# PlanktoscopeHat-v0_1-fab.net
KiCad netlist of a schematic drawn in EAGLE
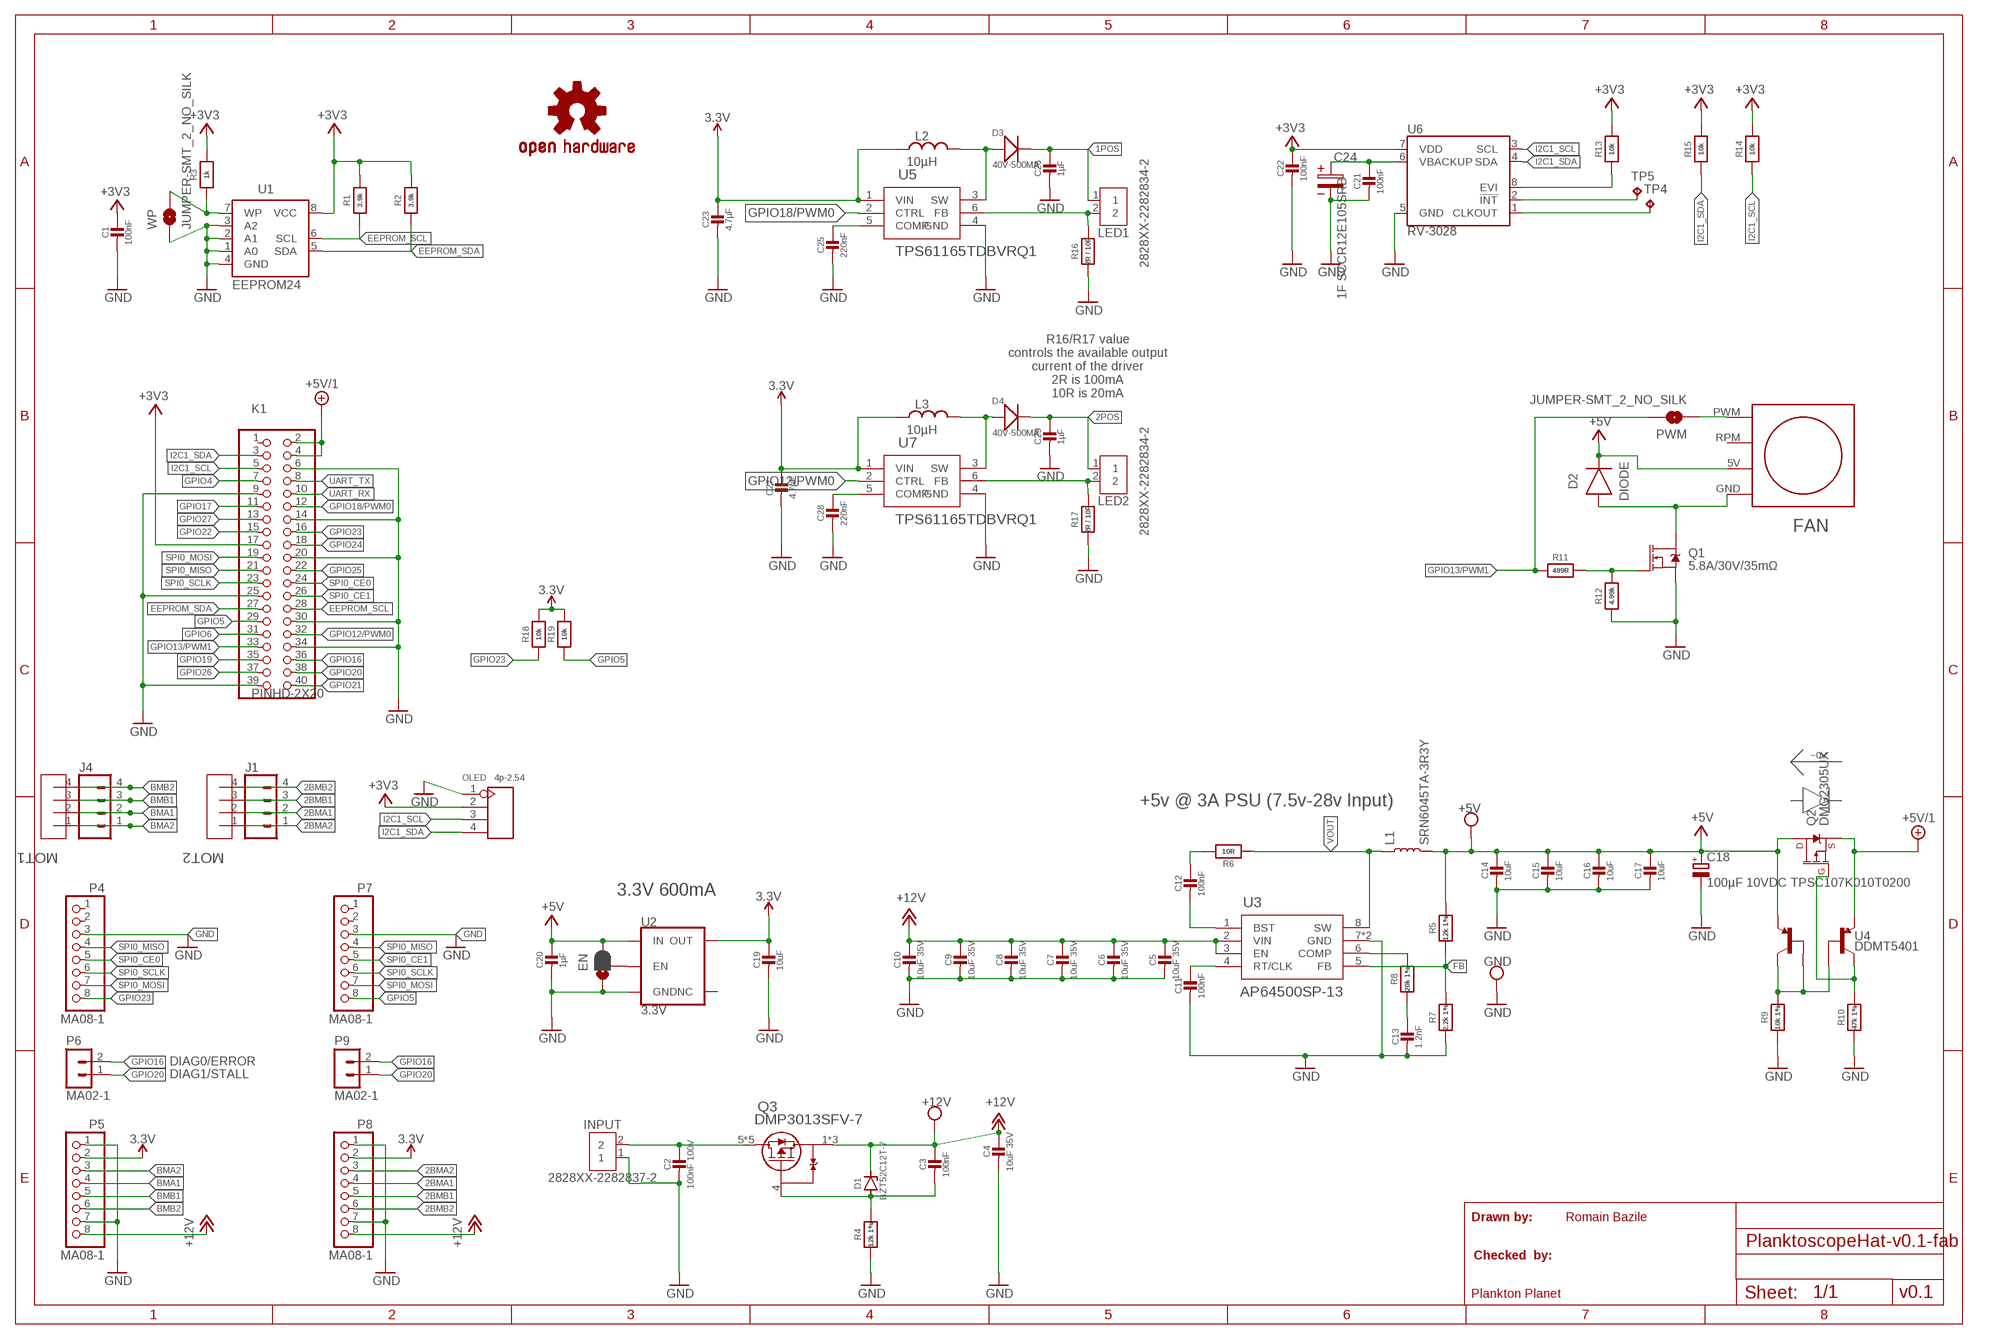
[diagram p0: schematic, sheet 1]

(export (version "E")
  (design (tool "Eeschema 10.0.6"))
  (components
    (comp (ref "+5V")
      (value "TESTPOINTPAD2MM")
      (footprint "eagle-import:TESTPOINT_PAD_2MM")
      (libsource (lib "eagle-import") (part "TESTPOINTPAD2MM"))
    )
    (comp (ref "+12V")
      (value "TESTPOINTPAD2MM")
      (footprint "eagle-import:TESTPOINT_PAD_2MM")
      (libsource (lib "eagle-import") (part "TESTPOINTPAD2MM"))
    )
    (comp (ref "C1")
      (value "100nF")
      (footprint "eagle-import:_0805MP")
      (libsource (lib "eagle-import") (part "CAP_CERAMIC_0805MP"))
    )
    (comp (ref "C2")
      (value "100nF 100V")
      (footprint "eagle-import:_0805MP")
      (libsource (lib "eagle-import") (part "CAP_CERAMIC_0805MP"))
    )
    (comp (ref "C3")
      (value "100nF")
      (footprint "eagle-import:_0805MP")
      (libsource (lib "eagle-import") (part "CAP_CERAMIC_0805MP"))
    )
    (comp (ref "C4")
      (value "10uF 35V")
      (footprint "eagle-import:_0805MP")
      (libsource (lib "eagle-import") (part "CAP_CERAMIC_0805MP"))
    )
    (comp (ref "C5")
      (value "10uF 35V")
      (footprint "eagle-import:_0805MP")
      (libsource (lib "eagle-import") (part "CAP_CERAMIC_0805MP"))
    )
    (comp (ref "C6")
      (value "10uF 35V")
      (footprint "eagle-import:_0805MP")
      (libsource (lib "eagle-import") (part "CAP_CERAMIC_0805MP"))
    )
    (comp (ref "C7")
      (value "10uF 35V")
      (footprint "eagle-import:_0805MP")
      (libsource (lib "eagle-import") (part "CAP_CERAMIC_0805MP"))
    )
    (comp (ref "C8")
      (value "10uF 35V")
      (footprint "eagle-import:_0805MP")
      (libsource (lib "eagle-import") (part "CAP_CERAMIC_0805MP"))
    )
    (comp (ref "C9")
      (value "10uF 35V")
      (footprint "eagle-import:_0805MP")
      (libsource (lib "eagle-import") (part "CAP_CERAMIC_0805MP"))
    )
    (comp (ref "C10")
      (value "10uF 35V")
      (footprint "eagle-import:_0805MP")
      (libsource (lib "eagle-import") (part "CAP_CERAMIC_0805MP"))
    )
    (comp (ref "C11")
      (value "100nF")
      (footprint "eagle-import:_0805MP")
      (libsource (lib "eagle-import") (part "CAP_CERAMIC_0805MP"))
    )
    (comp (ref "C12")
      (value "100nF")
      (footprint "eagle-import:_0805MP")
      (libsource (lib "eagle-import") (part "CAP_CERAMIC_0805MP"))
    )
    (comp (ref "C13")
      (value "1.2nF")
      (footprint "eagle-import:_0805MP")
      (libsource (lib "eagle-import") (part "CAP_CERAMIC_0805MP"))
    )
    (comp (ref "C14")
      (value "10uF")
      (footprint "eagle-import:_0805MP")
      (libsource (lib "eagle-import") (part "CAP_CERAMIC_0805MP"))
    )
    (comp (ref "C15")
      (value "10uF")
      (footprint "eagle-import:_0805MP")
      (libsource (lib "eagle-import") (part "CAP_CERAMIC_0805MP"))
    )
    (comp (ref "C16")
      (value "10uF")
      (footprint "eagle-import:_0805MP")
      (libsource (lib "eagle-import") (part "CAP_CERAMIC_0805MP"))
    )
    (comp (ref "C17")
      (value "10uF")
      (footprint "eagle-import:_0805MP")
      (libsource (lib "eagle-import") (part "CAP_CERAMIC_0805MP"))
    )
    (comp (ref "C18")
      (value "100µF 10VDC TPSC107K010T0200")
      (footprint "eagle-import:CAPMP6032X280N")
      (libsource (lib "eagle-import") (part "C-POLTANTALUM-2412(6032-METRIC)_"))
    )
    (comp (ref "C19")
      (value "10uF")
      (footprint "eagle-import:_0805MP")
      (libsource (lib "eagle-import") (part "CAP_CERAMIC_0805MP"))
    )
    (comp (ref "C20")
      (value "1µF")
      (footprint "eagle-import:_0805MP")
      (libsource (lib "eagle-import") (part "CAP_CERAMIC_0805MP"))
    )
    (comp (ref "C21")
      (value "100nF")
      (footprint "eagle-import:_0805MP")
      (libsource (lib "eagle-import") (part "CAP_CERAMIC_0805MP"))
    )
    (comp (ref "C22")
      (value "100nF")
      (footprint "eagle-import:_0805MP")
      (libsource (lib "eagle-import") (part "CAP_CERAMIC_0805MP"))
    )
    (comp (ref "C23")
      (value "4.7µF")
      (footprint "eagle-import:_0805MP")
      (libsource (lib "eagle-import") (part "CAP_CERAMIC_0805MP"))
    )
    (comp (ref "C24")
      (value "1F SCCR12E105SRB")
      (footprint "eagle-import:8X3.5X0.9(DXAXB)")
      (libsource (lib "eagle-import") (part "WCAP-PTHT_870135174001_8X8"))
    )
    (comp (ref "C25")
      (value "220nF")
      (footprint "eagle-import:_0805MP")
      (libsource (lib "eagle-import") (part "CAP_CERAMIC_0805MP"))
    )
    (comp (ref "C26")
      (value "1µF")
      (footprint "eagle-import:_0805MP")
      (libsource (lib "eagle-import") (part "CAP_CERAMIC_0805MP"))
    )
    (comp (ref "C27")
      (value "4.7µF")
      (footprint "eagle-import:_0805MP")
      (libsource (lib "eagle-import") (part "CAP_CERAMIC_0805MP"))
    )
    (comp (ref "C28")
      (value "220nF")
      (footprint "eagle-import:_0805MP")
      (libsource (lib "eagle-import") (part "CAP_CERAMIC_0805MP"))
    )
    (comp (ref "C29")
      (value "1µF")
      (footprint "eagle-import:_0805MP")
      (libsource (lib "eagle-import") (part "CAP_CERAMIC_0805MP"))
    )
    (comp (ref "D1")
      (value "BZT52C12T-7")
      (footprint "eagle-import:SODFL1608X70")
      (libsource (lib "eagle-import") (part "ZENERSODFL(1608-METRIC)_"))
    )
    (comp (ref "D2")
      (value "DIODE")
      (footprint "eagle-import:DIOM5226X290N")
      (libsource (lib "eagle-import") (part "DIODEDO-214AC(SMA)"))
    )
    (comp (ref "D3")
      (value "40V-500MA")
      (footprint "eagle-import:SOD-123")
      (fields (field (name "MPN") "B0540W"))
      (libsource (lib "eagle-import") (part "SMD-DIODE-SCHOTTKY-40V-500MA(SOD-123)"))
    )
    (comp (ref "D4")
      (value "40V-500MA")
      (footprint "eagle-import:SOD-123")
      (fields (field (name "MPN") "B0540W"))
      (libsource (lib "eagle-import") (part "SMD-DIODE-SCHOTTKY-40V-500MA(SOD-123)"))
    )
    (comp (ref "EN")
      (value "JUMPER-SMT_3_1-NC_PASTE_SILK")
      (footprint "eagle-import:SMT-JUMPER_3_1-NC_PASTE_SILK")
      (libsource (lib "eagle-import") (part "JUMPER-SMT_3_1-NC_PASTE_SILK"))
    )
    (comp (ref "FAN")
      (value "40MM_FAN")
      (footprint "eagle-import:40MM_FAN")
      (libsource (lib "eagle-import") (part "40MM_FAN"))
    )
    (comp (ref "GND")
      (value "TESTPOINTPAD2MM")
      (footprint "eagle-import:TESTPOINT_PAD_2MM")
      (libsource (lib "eagle-import") (part "TESTPOINTPAD2MM"))
    )
    (comp (ref "INPUT")
      (value "2828XX-2282837-2")
      (footprint "eagle-import:TERMBLK_508-2N")
      (fields
        (field (name "MANUFACTURER") "TE Connectivity")
        (field (name "MPN") "282837-2")
        (field (name "MPN_1") "TC0203620000G")
      )
      (libsource (lib "eagle-import") (part "2828XX-2282837-2"))
    )
    (comp (ref "J1")
      (value "CONN_04SCREW")
      (footprint "eagle-import:SCREWTERMINAL-3.5MM-4")
      (libsource (lib "eagle-import") (part "CONN_04SCREW"))
    )
    (comp (ref "J4")
      (value "CONN_04SCREW")
      (footprint "eagle-import:SCREWTERMINAL-3.5MM-4")
      (libsource (lib "eagle-import") (part "CONN_04SCREW"))
    )
    (comp (ref "K1")
      (value "PINHD-2X20")
      (footprint "eagle-import:2X20")
      (libsource (lib "eagle-import") (part "PINHD-2X20"))
    )
    (comp (ref "L1")
      (value "SRN6045TA-3R3Y")
      (footprint "eagle-import:SRN6045")
      (libsource (lib "eagle-import") (part "INDUCTOR-SRN6045-33UH"))
    )
    (comp (ref "L2")
      (value "10µH")
      (footprint "eagle-import:INDM3225X240")
      (fields (field (name "MPN") "CBC3225T100KR"))
      (libsource (lib "eagle-import") (part "LMOLDED-1210(3225-METRIC)_"))
    )
    (comp (ref "L3")
      (value "10µH")
      (footprint "eagle-import:INDM3225X240")
      (fields (field (name "MPN") "CBC3225T100KR"))
      (libsource (lib "eagle-import") (part "LMOLDED-1210(3225-METRIC)_"))
    )
    (comp (ref "LED1")
      (value "2828XX-2282834-2")
      (footprint "eagle-import:TERMBLK_254-2N")
      (libsource (lib "eagle-import") (part "2828XX-2282834-2"))
    )
    (comp (ref "LED2")
      (value "2828XX-2282834-2")
      (footprint "eagle-import:TERMBLK_254-2N")
      (libsource (lib "eagle-import") (part "2828XX-2282834-2"))
    )
    (comp (ref "LOGO1")
      (value "OSHW-LOGOL-COPPER")
      (footprint "eagle-import:OSHW-LOGO-L_COPPER")
      (libsource (lib "eagle-import") (part "OSHW-LOGOL-COPPER"))
    )
    (comp (ref "MOT1")
      (value "S4B-XH-SM4-TB(LF)(SN)")
      (footprint "eagle-import:CONN_S4B-XH-SM4-TB_JST")
      (fields (field (name "COPYRIGHT") "Copyright (C) 2018 Accelerated Designs. All rights reserved"))
      (libsource (lib "eagle-import") (part "S4B-XH-SM4-TB(LF)(SN)"))
    )
    (comp (ref "MOT2")
      (value "S4B-XH-SM4-TB(LF)(SN)")
      (footprint "eagle-import:CONN_S4B-XH-SM4-TB_JST")
      (fields (field (name "COPYRIGHT") "Copyright (C) 2018 Accelerated Designs. All rights reserved"))
      (libsource (lib "eagle-import") (part "S4B-XH-SM4-TB(LF)(SN)"))
    )
    (comp (ref "OLED")
      (value "4p-2.54")
      (footprint "eagle-import:H4-2.54")
      (fields (field (name "MPN") "P125-1104A0BS116A1"))
      (libsource (lib "eagle-import") (part "DIP-BLACK-MALE-HEADER-VERT(4P-2.54)"))
    )
    (comp (ref "P4")
      (value "MA08-1")
      (footprint "eagle-import:1X08-S")
      (libsource (lib "eagle-import") (part "PINHD-1X08_2.54-S"))
    )
    (comp (ref "P5")
      (value "MA08-1")
      (footprint "eagle-import:1X08-S")
      (libsource (lib "eagle-import") (part "PINHD-1X08_2.54-S"))
    )
    (comp (ref "P6")
      (value "MA02-1")
      (footprint "eagle-import:MA02-1")
      (libsource (lib "eagle-import") (part "MA02-1"))
    )
    (comp (ref "P7")
      (value "MA08-1")
      (footprint "eagle-import:1X08-S")
      (libsource (lib "eagle-import") (part "PINHD-1X08_2.54-S"))
    )
    (comp (ref "P8")
      (value "MA08-1")
      (footprint "eagle-import:1X08-S")
      (libsource (lib "eagle-import") (part "PINHD-1X08_2.54-S"))
    )
    (comp (ref "P9")
      (value "MA02-1")
      (footprint "eagle-import:MA02-1")
      (libsource (lib "eagle-import") (part "MA02-1"))
    )
    (comp (ref "PWM")
      (value "JUMPER-SMT_2_NO_SILK")
      (footprint "eagle-import:SMT-JUMPER_2_NO_SILK")
      (libsource (lib "eagle-import") (part "JUMPER-SMT_2_NO_SILK"))
    )
    (comp (ref "Q1")
      (value "5.8A/30V/35mΩ")
      (footprint "eagle-import:SOT23-3")
      (libsource (lib "eagle-import") (part "MOSFET-NCH-AO3404A"))
    )
    (comp (ref "Q2")
      (value "DMG2305UX")
      (footprint "eagle-import:SOT23-3")
      (libsource (lib "eagle-import") (part "MOSFET_PCH-DMG2305UX-7"))
    )
    (comp (ref "Q3")
      (value "DMP3013SFV-7")
      (footprint "eagle-import:POWERDI3333-8_UX_DIO")
      (fields (field (name "COPYRIGHT") "Copyright (C) 2018 Accelerated Designs. All rights reserved"))
      (libsource (lib "eagle-import") (part "DMP3013SFV-7"))
    )
    (comp (ref "R1")
      (value "3.9k")
      (footprint "eagle-import:_0805MP")
      (libsource (lib "eagle-import") (part "RESISTOR_0805MP"))
    )
    (comp (ref "R2")
      (value "3.9k")
      (footprint "eagle-import:_0805MP")
      (libsource (lib "eagle-import") (part "RESISTOR_0805MP"))
    )
    (comp (ref "R3")
      (value "1k")
      (footprint "eagle-import:_0805MP")
      (libsource (lib "eagle-import") (part "RESISTOR_0805MP"))
    )
    (comp (ref "R4")
      (value "12k 1%")
      (footprint "eagle-import:_0805MP")
      (libsource (lib "eagle-import") (part "RESISTOR_0805MP"))
    )
    (comp (ref "R5")
      (value "12k 1%")
      (footprint "eagle-import:_0805MP")
      (libsource (lib "eagle-import") (part "RESISTOR_0805MP"))
    )
    (comp (ref "R6")
      (value "10R")
      (footprint "eagle-import:_0805MP")
      (libsource (lib "eagle-import") (part "RESISTOR_0805MP"))
    )
    (comp (ref "R7")
      (value "2.2k 1%")
      (footprint "eagle-import:_0805MP")
      (libsource (lib "eagle-import") (part "RESISTOR_0805MP"))
    )
    (comp (ref "R8")
      (value "20k 1%")
      (footprint "eagle-import:_0805MP")
      (libsource (lib "eagle-import") (part "RESISTOR_0805MP"))
    )
    (comp (ref "R9")
      (value "10k 1%")
      (footprint "eagle-import:_0805MP")
      (libsource (lib "eagle-import") (part "RESISTOR_0805MP"))
    )
    (comp (ref "R10")
      (value "47k 1%")
      (footprint "eagle-import:_0805MP")
      (libsource (lib "eagle-import") (part "RESISTOR_0805MP"))
    )
    (comp (ref "R11")
      (value "499R")
      (footprint "eagle-import:_0805MP")
      (libsource (lib "eagle-import") (part "RESISTOR_0805MP"))
    )
    (comp (ref "R12")
      (value "4.99k")
      (footprint "eagle-import:_0805MP")
      (libsource (lib "eagle-import") (part "RESISTOR_0805MP"))
    )
    (comp (ref "R13")
      (value "10k")
      (footprint "eagle-import:_0805MP")
      (libsource (lib "eagle-import") (part "RESISTOR_0805MP"))
    )
    (comp (ref "R14")
      (value "10k")
      (footprint "eagle-import:_0805MP")
      (libsource (lib "eagle-import") (part "RESISTOR_0805MP"))
    )
    (comp (ref "R15")
      (value "10k")
      (footprint "eagle-import:_0805MP")
      (libsource (lib "eagle-import") (part "RESISTOR_0805MP"))
    )
    (comp (ref "R16")
      (value "2R / 10R")
      (footprint "eagle-import:_0805MP")
      (libsource (lib "eagle-import") (part "RESISTOR_0805MP"))
    )
    (comp (ref "R17")
      (value "2R / 10R")
      (footprint "eagle-import:_0805MP")
      (libsource (lib "eagle-import") (part "RESISTOR_0805MP"))
    )
    (comp (ref "R18")
      (value "10k")
      (footprint "eagle-import:_0805MP")
      (libsource (lib "eagle-import") (part "RESISTOR_0805MP"))
    )
    (comp (ref "R19")
      (value "10k")
      (footprint "eagle-import:_0805MP")
      (libsource (lib "eagle-import") (part "RESISTOR_0805MP"))
    )
    (comp (ref "TP4")
      (value "TPB1,27")
      (footprint "eagle-import:B1,27")
      (libsource (lib "eagle-import") (part "TPB1,27"))
    )
    (comp (ref "TP5")
      (value "TPB1,27")
      (footprint "eagle-import:B1,27")
      (libsource (lib "eagle-import") (part "TPB1,27"))
    )
    (comp (ref "U1")
      (value "EEPROM24")
      (footprint "eagle-import:SOIC8")
      (libsource (lib "eagle-import") (part "EEPROM24"))
    )
    (comp (ref "U2")
      (value "3.3V")
      (footprint "eagle-import:SOT23-5")
      (libsource (lib "eagle-import") (part "V_REG_AP2112K-3.3V"))
    )
    (comp (ref "U3")
      (value "AP64500SP-13")
      (footprint "eagle-import:SO-8EP_DIO")
      (fields (field (name "COPYRIGHT") "Copyright (C) 2018 Accelerated Designs. All rights reserved"))
      (libsource (lib "eagle-import") (part "AP64500SP-13"))
    )
    (comp (ref "U4")
      (value "DDMT5401")
      (footprint "eagle-import:SOT26")
      (libsource (lib "eagle-import") (part "DDMT5401"))
    )
    (comp (ref "U5")
      (value "TPS61165TDBVRQ1")
      (footprint "eagle-import:DBV6")
      (fields
        (field (name "GENERIC_PART_NUMBER") "TPS61165-Q1")
        (field (name "MANUFACTURER") "Texas Instruments")
      )
      (libsource (lib "eagle-import") (part "TPS61165TDBVRQ1"))
    )
    (comp (ref "U6")
      (value "RV-3028")
      (footprint "eagle-import:RV-3028")
      (libsource (lib "eagle-import") (part "RV-3028"))
    )
    (comp (ref "U7")
      (value "TPS61165TDBVRQ1")
      (footprint "eagle-import:DBV6")
      (fields
        (field (name "GENERIC_PART_NUMBER") "TPS61165-Q1")
        (field (name "MANUFACTURER") "Texas Instruments")
      )
      (libsource (lib "eagle-import") (part "TPS61165TDBVRQ1"))
    )
    (comp (ref "WP")
      (value "JUMPER-SMT_2_NO_SILK")
      (footprint "eagle-import:SMT-JUMPER_2_NO_SILK")
      (libsource (lib "eagle-import") (part "JUMPER-SMT_2_NO_SILK"))
    )
  )
  (nets
    (net (code "1") (name "+3V3") (class "Default")
      (node (ref "C1") (pin "1") (pinfunction "1_1") (pintype "passive"))
      (node (ref "C22") (pin "1") (pinfunction "1_1") (pintype "passive"))
      (node (ref "K1") (pin "17") (pinfunction "17_17") (pintype "passive"))
      (node (ref "OLED") (pin "2") (pinfunction "P$2_2") (pintype "bidirectional"))
      (node (ref "R1") (pin "2") (pinfunction "2_2") (pintype "passive"))
      (node (ref "R13") (pin "2") (pinfunction "2_2") (pintype "passive"))
      (node (ref "R14") (pin "2") (pinfunction "2_2") (pintype "passive"))
      (node (ref "R15") (pin "2") (pinfunction "2_2") (pintype "passive"))
      (node (ref "R2") (pin "2") (pinfunction "2_2") (pintype "passive"))
      (node (ref "R3") (pin "2") (pinfunction "2_2") (pintype "passive"))
      (node (ref "U1") (pin "8") (pinfunction "VCC_8") (pintype "power_in"))
      (node (ref "U6") (pin "7") (pinfunction "VDD_7") (pintype "bidirectional"))
    )
    (net (code "2") (name "+5V") (class "Default")
      (node (ref "+5V") (pin "P$1") (pinfunction "P$1_P$1") (pintype "bidirectional"))
      (node (ref "C14") (pin "1") (pinfunction "1_1") (pintype "passive"))
      (node (ref "C15") (pin "1") (pinfunction "1_1") (pintype "passive"))
      (node (ref "C16") (pin "1") (pinfunction "1_1") (pintype "passive"))
      (node (ref "C17") (pin "1") (pinfunction "1_1") (pintype "passive"))
      (node (ref "C18") (pin "1") (pinfunction "+_1") (pintype "passive"))
      (node (ref "C20") (pin "1") (pinfunction "1_1") (pintype "passive"))
      (node (ref "D2") (pin "1") (pinfunction "C_1") (pintype "passive"))
      (node (ref "EN") (pin "3") (pinfunction "3_3") (pintype "passive"))
      (node (ref "FAN") (pin "5V") (pinfunction "+5V_5V") (pintype "passive"))
      (node (ref "L1") (pin "2") (pinfunction "2_2") (pintype "passive"))
      (node (ref "Q2") (pin "3") (pinfunction "D_3") (pintype "bidirectional"))
      (node (ref "R5") (pin "2") (pinfunction "2_2") (pintype "passive"))
      (node (ref "U2") (pin "1") (pinfunction "IN_1") (pintype "input"))
      (node (ref "U4") (pin "D1") (pinfunction "6_D1") (pintype "passive"))
    )
    (net (code "3") (name "+5V{slash}1") (class "Default")
      (node (ref "K1") (pin "2") (pinfunction "2_2") (pintype "passive"))
      (node (ref "K1") (pin "4") (pinfunction "4_4") (pintype "passive"))
      (node (ref "Q2") (pin "2") (pinfunction "S_2") (pintype "bidirectional"))
      (node (ref "U4") (pin "S1") (pinfunction "5_S1") (pintype "passive"))
    )
    (net (code "4") (name "+12V") (class "Default")
      (node (ref "+12V") (pin "P$1") (pinfunction "P$1_P$1") (pintype "bidirectional"))
      (node (ref "C10") (pin "1") (pinfunction "1_1") (pintype "passive"))
      (node (ref "C3") (pin "1") (pinfunction "1_1") (pintype "passive"))
      (node (ref "C4") (pin "1") (pinfunction "1_1") (pintype "passive"))
      (node (ref "C5") (pin "1") (pinfunction "1_1") (pintype "passive"))
      (node (ref "C6") (pin "1") (pinfunction "1_1") (pintype "passive"))
      (node (ref "C7") (pin "1") (pinfunction "1_1") (pintype "passive"))
      (node (ref "C8") (pin "1") (pinfunction "1_1") (pintype "passive"))
      (node (ref "C9") (pin "1") (pinfunction "1_1") (pintype "passive"))
      (node (ref "D1") (pin "1") (pinfunction "C_1") (pintype "passive"))
      (node (ref "P5") (pin "8") (pinfunction "8_8") (pintype "passive"))
      (node (ref "P8") (pin "8") (pinfunction "8_8") (pintype "passive"))
      (node (ref "Q3") (pin "1") (pinfunction "S_1") (pintype "passive"))
      (node (ref "Q3") (pin "2") (pinfunction "S_2") (pintype "passive"))
      (node (ref "Q3") (pin "3") (pinfunction "S_3") (pintype "passive"))
      (node (ref "U3") (pin "2") (pinfunction "VIN_2") (pintype "power_in"))
      (node (ref "U3") (pin "3") (pinfunction "EN_3") (pintype "input"))
    )
    (net (code "5") (name "1POS") (class "Default")
      (node (ref "C26") (pin "1") (pinfunction "1_1") (pintype "passive"))
      (node (ref "D3") (pin "-") (pinfunction "-_-") (pintype "passive"))
      (node (ref "LED1") (pin "1") (pinfunction "1_1") (pintype "bidirectional"))
    )
    (net (code "6") (name "2BMA1") (class "Default")
      (node (ref "J1") (pin "2") (pinfunction "2_2") (pintype "passive"))
      (node (ref "MOT2") (pin "2") (pinfunction "2_2") (pintype "passive"))
      (node (ref "P8") (pin "4") (pinfunction "4_4") (pintype "passive"))
    )
    (net (code "7") (name "2BMA2") (class "Default")
      (node (ref "J1") (pin "1") (pinfunction "1_1") (pintype "passive"))
      (node (ref "MOT2") (pin "1") (pinfunction "1_1") (pintype "passive"))
      (node (ref "P8") (pin "3") (pinfunction "3_3") (pintype "passive"))
    )
    (net (code "8") (name "2BMB1") (class "Default")
      (node (ref "J1") (pin "3") (pinfunction "3_3") (pintype "passive"))
      (node (ref "MOT2") (pin "3") (pinfunction "3_3") (pintype "passive"))
      (node (ref "P8") (pin "5") (pinfunction "5_5") (pintype "passive"))
    )
    (net (code "9") (name "2BMB2") (class "Default")
      (node (ref "J1") (pin "4") (pinfunction "4_4") (pintype "passive"))
      (node (ref "MOT2") (pin "4") (pinfunction "4_4") (pintype "passive"))
      (node (ref "P8") (pin "6") (pinfunction "6_6") (pintype "passive"))
    )
    (net (code "10") (name "2POS") (class "Default")
      (node (ref "C29") (pin "1") (pinfunction "1_1") (pintype "passive"))
      (node (ref "D4") (pin "-") (pinfunction "-_-") (pintype "passive"))
      (node (ref "LED2") (pin "1") (pinfunction "1_1") (pintype "bidirectional"))
    )
    (net (code "11") (name "3.3V") (class "Default")
      (node (ref "C19") (pin "1") (pinfunction "1_1") (pintype "passive"))
      (node (ref "C23") (pin "1") (pinfunction "1_1") (pintype "passive"))
      (node (ref "C27") (pin "1") (pinfunction "1_1") (pintype "passive"))
      (node (ref "L2") (pin "1") (pinfunction "1_1") (pintype "passive"))
      (node (ref "L3") (pin "1") (pinfunction "1_1") (pintype "passive"))
      (node (ref "P5") (pin "2") (pinfunction "2_2") (pintype "passive"))
      (node (ref "P8") (pin "2") (pinfunction "2_2") (pintype "passive"))
      (node (ref "R18") (pin "2") (pinfunction "2_2") (pintype "passive"))
      (node (ref "R19") (pin "2") (pinfunction "2_2") (pintype "passive"))
      (node (ref "U2") (pin "5") (pinfunction "OUT_5") (pintype "passive"))
      (node (ref "U5") (pin "1") (pinfunction "VIN_1") (pintype "input"))
      (node (ref "U7") (pin "1") (pinfunction "VIN_1") (pintype "input"))
    )
    (net (code "12") (name "BMA1") (class "Default")
      (node (ref "J4") (pin "2") (pinfunction "2_2") (pintype "passive"))
      (node (ref "MOT1") (pin "2") (pinfunction "2_2") (pintype "passive"))
      (node (ref "P5") (pin "4") (pinfunction "4_4") (pintype "passive"))
    )
    (net (code "13") (name "BMA2") (class "Default")
      (node (ref "J4") (pin "1") (pinfunction "1_1") (pintype "passive"))
      (node (ref "MOT1") (pin "1") (pinfunction "1_1") (pintype "passive"))
      (node (ref "P5") (pin "3") (pinfunction "3_3") (pintype "passive"))
    )
    (net (code "14") (name "BMB1") (class "Default")
      (node (ref "J4") (pin "3") (pinfunction "3_3") (pintype "passive"))
      (node (ref "MOT1") (pin "3") (pinfunction "3_3") (pintype "passive"))
      (node (ref "P5") (pin "5") (pinfunction "5_5") (pintype "passive"))
    )
    (net (code "15") (name "BMB2") (class "Default")
      (node (ref "J4") (pin "4") (pinfunction "4_4") (pintype "passive"))
      (node (ref "MOT1") (pin "4") (pinfunction "4_4") (pintype "passive"))
      (node (ref "P5") (pin "6") (pinfunction "6_6") (pintype "passive"))
    )
    (net (code "16") (name "EEPROM_SCL") (class "Default")
      (node (ref "K1") (pin "28") (pinfunction "28_28") (pintype "passive"))
      (node (ref "R1") (pin "1") (pinfunction "1_1") (pintype "passive"))
      (node (ref "U1") (pin "6") (pinfunction "SCL_6") (pintype "input"))
    )
    (net (code "17") (name "EEPROM_SDA") (class "Default")
      (node (ref "K1") (pin "27") (pinfunction "27_27") (pintype "passive"))
      (node (ref "R2") (pin "1") (pinfunction "1_1") (pintype "passive"))
      (node (ref "U1") (pin "5") (pinfunction "SDA_5") (pintype "bidirectional"))
    )
    (net (code "18") (name "FB") (class "Default")
      (node (ref "R5") (pin "1") (pinfunction "1_1") (pintype "passive"))
      (node (ref "R7") (pin "2") (pinfunction "2_2") (pintype "passive"))
      (node (ref "U3") (pin "5") (pinfunction "FB_5") (pintype "passive"))
    )
    (net (code "19") (name "GND") (class "Default")
      (node (ref "C1") (pin "2") (pinfunction "2_2") (pintype "passive"))
      (node (ref "C10") (pin "2") (pinfunction "2_2") (pintype "passive"))
      (node (ref "C11") (pin "2") (pinfunction "2_2") (pintype "passive"))
      (node (ref "C13") (pin "2") (pinfunction "2_2") (pintype "passive"))
      (node (ref "C14") (pin "2") (pinfunction "2_2") (pintype "passive"))
      (node (ref "C15") (pin "2") (pinfunction "2_2") (pintype "passive"))
      (node (ref "C16") (pin "2") (pinfunction "2_2") (pintype "passive"))
      (node (ref "C17") (pin "2") (pinfunction "2_2") (pintype "passive"))
      (node (ref "C18") (pin "2") (pinfunction "-_2") (pintype "passive"))
      (node (ref "C19") (pin "2") (pinfunction "2_2") (pintype "passive"))
      (node (ref "C2") (pin "2") (pinfunction "2_2") (pintype "passive"))
      (node (ref "C20") (pin "2") (pinfunction "2_2") (pintype "passive"))
      (node (ref "C21") (pin "2") (pinfunction "2_2") (pintype "passive"))
      (node (ref "C22") (pin "2") (pinfunction "2_2") (pintype "passive"))
      (node (ref "C23") (pin "2") (pinfunction "2_2") (pintype "passive"))
      (node (ref "C24") (pin "2") (pinfunction "2_2") (pintype "passive"))
      (node (ref "C25") (pin "2") (pinfunction "2_2") (pintype "passive"))
      (node (ref "C26") (pin "2") (pinfunction "2_2") (pintype "passive"))
      (node (ref "C27") (pin "2") (pinfunction "2_2") (pintype "passive"))
      (node (ref "C28") (pin "2") (pinfunction "2_2") (pintype "passive"))
      (node (ref "C29") (pin "2") (pinfunction "2_2") (pintype "passive"))
      (node (ref "C4") (pin "2") (pinfunction "2_2") (pintype "passive"))
      (node (ref "C5") (pin "2") (pinfunction "2_2") (pintype "passive"))
      (node (ref "C6") (pin "2") (pinfunction "2_2") (pintype "passive"))
      (node (ref "C7") (pin "2") (pinfunction "2_2") (pintype "passive"))
      (node (ref "C8") (pin "2") (pinfunction "2_2") (pintype "passive"))
      (node (ref "C9") (pin "2") (pinfunction "2_2") (pintype "passive"))
      (node (ref "EN") (pin "1") (pinfunction "1_1") (pintype "passive"))
      (node (ref "GND") (pin "P$1") (pinfunction "P$1_P$1") (pintype "bidirectional"))
      (node (ref "INPUT") (pin "1") (pinfunction "1_1") (pintype "bidirectional"))
      (node (ref "K1") (pin "14") (pinfunction "14_14") (pintype "passive"))
      (node (ref "K1") (pin "20") (pinfunction "20_20") (pintype "passive"))
      (node (ref "K1") (pin "25") (pinfunction "25_25") (pintype "passive"))
      (node (ref "K1") (pin "30") (pinfunction "30_30") (pintype "passive"))
      (node (ref "K1") (pin "34") (pinfunction "34_34") (pintype "passive"))
      (node (ref "K1") (pin "39") (pinfunction "39_39") (pintype "passive"))
      (node (ref "K1") (pin "6") (pinfunction "6_6") (pintype "passive"))
      (node (ref "K1") (pin "9") (pinfunction "9_9") (pintype "passive"))
      (node (ref "OLED") (pin "1") (pinfunction "P$1_1") (pintype "bidirectional"))
      (node (ref "P4") (pin "3") (pinfunction "3_3") (pintype "passive"))
      (node (ref "P5") (pin "1") (pinfunction "1_1") (pintype "passive"))
      (node (ref "P5") (pin "7") (pinfunction "7_7") (pintype "passive"))
      (node (ref "P7") (pin "3") (pinfunction "3_3") (pintype "passive"))
      (node (ref "P8") (pin "1") (pinfunction "1_1") (pintype "passive"))
      (node (ref "P8") (pin "7") (pinfunction "7_7") (pintype "passive"))
      (node (ref "Q1") (pin "2") (pinfunction "S_2") (pintype "bidirectional"))
      (node (ref "R10") (pin "1") (pinfunction "1_1") (pintype "passive"))
      (node (ref "R12") (pin "1") (pinfunction "1_1") (pintype "passive"))
      (node (ref "R16") (pin "1") (pinfunction "1_1") (pintype "passive"))
      (node (ref "R17") (pin "1") (pinfunction "1_1") (pintype "passive"))
      (node (ref "R4") (pin "1") (pinfunction "1_1") (pintype "passive"))
      (node (ref "R7") (pin "1") (pinfunction "1_1") (pintype "passive"))
      (node (ref "R9") (pin "1") (pinfunction "1_1") (pintype "passive"))
      (node (ref "U1") (pin "1") (pinfunction "A0_1") (pintype "input"))
      (node (ref "U1") (pin "2") (pinfunction "A1_2") (pintype "input"))
      (node (ref "U1") (pin "3") (pinfunction "A2_3") (pintype "input"))
      (node (ref "U1") (pin "4") (pinfunction "GND_4") (pintype "power_in"))
      (node (ref "U2") (pin "2") (pinfunction "GND_2") (pintype "input"))
      (node (ref "U3") (pin "7") (pinfunction "GND_7") (pintype "passive"))
      (node (ref "U3") (pin "EPAD") (pinfunction "GND_EPAD") (pintype "passive"))
      (node (ref "U5") (pin "4") (pinfunction "GND_4") (pintype "output"))
      (node (ref "U6") (pin "5") (pinfunction "GND_5") (pintype "bidirectional"))
      (node (ref "U7") (pin "4") (pinfunction "GND_4") (pintype "output"))
      (node (ref "WP") (pin "1") (pinfunction "1_1") (pintype "passive"))
    )
    (net (code "20") (name "GPIO4") (class "Default")
      (node (ref "K1") (pin "7") (pinfunction "7_7") (pintype "passive"))
    )
    (net (code "21") (name "GPIO5") (class "Default")
      (node (ref "K1") (pin "29") (pinfunction "29_29") (pintype "passive"))
      (node (ref "P7") (pin "8") (pinfunction "8_8") (pintype "passive"))
      (node (ref "R19") (pin "1") (pinfunction "1_1") (pintype "passive"))
    )
    (net (code "22") (name "GPIO6") (class "Default")
      (node (ref "K1") (pin "31") (pinfunction "31_31") (pintype "passive"))
    )
    (net (code "23") (name "GPIO12{slash}PWM0") (class "Default")
      (node (ref "K1") (pin "32") (pinfunction "32_32") (pintype "passive"))
      (node (ref "U7") (pin "2") (pinfunction "CTRL_2") (pintype "input"))
    )
    (net (code "24") (name "GPIO13{slash}PWM1") (class "Default")
      (node (ref "K1") (pin "33") (pinfunction "33_33") (pintype "passive"))
      (node (ref "PWM") (pin "2") (pinfunction "2_2") (pintype "passive"))
      (node (ref "R11") (pin "1") (pinfunction "1_1") (pintype "passive"))
    )
    (net (code "25") (name "GPIO16") (class "Default")
      (node (ref "K1") (pin "36") (pinfunction "36_36") (pintype "passive"))
      (node (ref "P6") (pin "2") (pinfunction "2_2") (pintype "passive"))
      (node (ref "P9") (pin "2") (pinfunction "2_2") (pintype "passive"))
    )
    (net (code "26") (name "GPIO17") (class "Default")
      (node (ref "K1") (pin "11") (pinfunction "11_11") (pintype "passive"))
    )
    (net (code "27") (name "GPIO18{slash}PWM0") (class "Default")
      (node (ref "K1") (pin "12") (pinfunction "12_12") (pintype "passive"))
      (node (ref "U5") (pin "2") (pinfunction "CTRL_2") (pintype "input"))
    )
    (net (code "28") (name "GPIO19") (class "Default")
      (node (ref "K1") (pin "35") (pinfunction "35_35") (pintype "passive"))
    )
    (net (code "29") (name "GPIO20") (class "Default")
      (node (ref "K1") (pin "38") (pinfunction "38_38") (pintype "passive"))
      (node (ref "P6") (pin "1") (pinfunction "1_1") (pintype "passive"))
      (node (ref "P9") (pin "1") (pinfunction "1_1") (pintype "passive"))
    )
    (net (code "30") (name "GPIO21") (class "Default")
      (node (ref "K1") (pin "40") (pinfunction "40_40") (pintype "passive"))
    )
    (net (code "31") (name "GPIO22") (class "Default")
      (node (ref "K1") (pin "15") (pinfunction "15_15") (pintype "passive"))
    )
    (net (code "32") (name "GPIO23") (class "Default")
      (node (ref "K1") (pin "16") (pinfunction "16_16") (pintype "passive"))
      (node (ref "P4") (pin "8") (pinfunction "8_8") (pintype "passive"))
      (node (ref "R18") (pin "1") (pinfunction "1_1") (pintype "passive"))
    )
    (net (code "33") (name "GPIO24") (class "Default")
      (node (ref "K1") (pin "18") (pinfunction "18_18") (pintype "passive"))
    )
    (net (code "34") (name "GPIO25") (class "Default")
      (node (ref "K1") (pin "22") (pinfunction "22_22") (pintype "passive"))
    )
    (net (code "35") (name "GPIO26") (class "Default")
      (node (ref "K1") (pin "37") (pinfunction "37_37") (pintype "passive"))
    )
    (net (code "36") (name "GPIO27") (class "Default")
      (node (ref "K1") (pin "13") (pinfunction "13_13") (pintype "passive"))
    )
    (net (code "37") (name "I2C1_SCL") (class "Default")
      (node (ref "K1") (pin "5") (pinfunction "5_5") (pintype "passive"))
      (node (ref "OLED") (pin "3") (pinfunction "P$3_3") (pintype "bidirectional"))
      (node (ref "R14") (pin "1") (pinfunction "1_1") (pintype "passive"))
      (node (ref "U6") (pin "3") (pinfunction "SCL_3") (pintype "bidirectional"))
    )
    (net (code "38") (name "I2C1_SDA") (class "Default")
      (node (ref "K1") (pin "3") (pinfunction "3_3") (pintype "passive"))
      (node (ref "OLED") (pin "4") (pinfunction "P$4_4") (pintype "bidirectional"))
      (node (ref "R15") (pin "1") (pinfunction "1_1") (pintype "passive"))
      (node (ref "U6") (pin "4") (pinfunction "SDA_4") (pintype "bidirectional"))
    )
    (net (code "39") (name "Net-(C2-Pad1)") (class "Default")
      (node (ref "C2") (pin "1") (pinfunction "1_1") (pintype "passive"))
      (node (ref "INPUT") (pin "2") (pinfunction "2_2") (pintype "bidirectional"))
      (node (ref "Q3") (pin "5") (pinfunction "D_5") (pintype "passive"))
      (node (ref "Q3") (pin "6") (pinfunction "D_6") (pintype "passive"))
      (node (ref "Q3") (pin "7") (pinfunction "D_7") (pintype "passive"))
      (node (ref "Q3") (pin "8") (pinfunction "D_8") (pintype "passive"))
      (node (ref "Q3") (pin "9") (pinfunction "D_9") (pintype "passive"))
    )
    (net (code "40") (name "Net-(C12-Pad1)") (class "Default")
      (node (ref "C12") (pin "1") (pinfunction "1_1") (pintype "passive"))
      (node (ref "R6") (pin "2") (pinfunction "2_2") (pintype "passive"))
    )
    (net (code "41") (name "Net-(C13-Pad1)") (class "Default")
      (node (ref "C13") (pin "1") (pinfunction "1_1") (pintype "passive"))
      (node (ref "R8") (pin "1") (pinfunction "1_1") (pintype "passive"))
    )
    (net (code "42") (name "Net-(D1-A)") (class "Default")
      (node (ref "C3") (pin "2") (pinfunction "2_2") (pintype "passive"))
      (node (ref "D1") (pin "2") (pinfunction "A_2") (pintype "passive"))
      (node (ref "Q3") (pin "4") (pinfunction "G_4") (pintype "passive"))
      (node (ref "R4") (pin "2") (pinfunction "2_2") (pintype "passive"))
    )
    (net (code "43") (name "Net-(D2-A)") (class "Default")
      (node (ref "D2") (pin "2") (pinfunction "A_2") (pintype "passive"))
      (node (ref "FAN") (pin "GND") (pinfunction "GND_GND") (pintype "passive"))
      (node (ref "Q1") (pin "3") (pinfunction "D_3") (pintype "bidirectional"))
    )
    (net (code "44") (name "Net-(FAN-PadPWM)") (class "Default")
      (node (ref "FAN") (pin "PWM") (pinfunction "PWM_PWM") (pintype "passive"))
      (node (ref "PWM") (pin "1") (pinfunction "1_1") (pintype "passive"))
    )
    (net (code "45") (name "Net-(Q1-G)") (class "Default")
      (node (ref "Q1") (pin "1") (pinfunction "G_1") (pintype "bidirectional"))
      (node (ref "R11") (pin "2") (pinfunction "2_2") (pintype "passive"))
      (node (ref "R12") (pin "2") (pinfunction "2_2") (pintype "passive"))
    )
    (net (code "46") (name "Net-(Q2-G)") (class "Default")
      (node (ref "Q2") (pin "1") (pinfunction "G_1") (pintype "bidirectional"))
      (node (ref "R10") (pin "2") (pinfunction "2_2") (pintype "passive"))
      (node (ref "U4") (pin "D2") (pinfunction "4_D2") (pintype "passive"))
    )
    (net (code "47") (name "Net-(U1-WP)") (class "Default")
      (node (ref "R3") (pin "1") (pinfunction "1_1") (pintype "passive"))
      (node (ref "U1") (pin "7") (pinfunction "WP_7") (pintype "input"))
      (node (ref "WP") (pin "2") (pinfunction "2_2") (pintype "passive"))
    )
    (net (code "48") (name "Net-(U2-EN)") (class "Default")
      (node (ref "EN") (pin "2") (pinfunction "2_2") (pintype "passive"))
      (node (ref "U2") (pin "3") (pinfunction "EN_3") (pintype "input"))
    )
    (net (code "49") (name "Net-(U3-BST)") (class "Default")
      (node (ref "C12") (pin "2") (pinfunction "2_2") (pintype "passive"))
      (node (ref "U3") (pin "1") (pinfunction "BST_1") (pintype "power_in"))
    )
    (net (code "50") (name "Net-(U3-COMP)") (class "Default")
      (node (ref "R8") (pin "2") (pinfunction "2_2") (pintype "passive"))
      (node (ref "U3") (pin "6") (pinfunction "COMP_6") (pintype "passive"))
    )
    (net (code "51") (name "Net-(U3-RT{slash}CLK)") (class "Default")
      (node (ref "C11") (pin "1") (pinfunction "1_1") (pintype "passive"))
      (node (ref "U3") (pin "4") (pinfunction "RT/CLK_4") (pintype "passive"))
    )
    (net (code "52") (name "Net-(U4-1)") (class "Default")
      (node (ref "R9") (pin "2") (pinfunction "2_2") (pintype "passive"))
      (node (ref "U4") (pin "G1") (pinfunction "1_G1") (pintype "passive"))
      (node (ref "U4") (pin "G2") (pinfunction "3_G2") (pintype "passive"))
      (node (ref "U4") (pin "S2") (pinfunction "2_S2") (pintype "passive"))
    )
    (net (code "53") (name "Net-(U5-COMP)") (class "Default")
      (node (ref "C25") (pin "1") (pinfunction "1_1") (pintype "passive"))
      (node (ref "U5") (pin "5") (pinfunction "COMP_5") (pintype "output"))
    )
    (net (code "54") (name "Net-(U5-FB)") (class "Default")
      (node (ref "LED1") (pin "2") (pinfunction "2_2") (pintype "bidirectional"))
      (node (ref "R16") (pin "2") (pinfunction "2_2") (pintype "passive"))
      (node (ref "U5") (pin "6") (pinfunction "FB_6") (pintype "input"))
    )
    (net (code "55") (name "Net-(U5-SW)") (class "Default")
      (node (ref "D3") (pin "+") (pinfunction "+_+") (pintype "passive"))
      (node (ref "L2") (pin "2") (pinfunction "2_2") (pintype "passive"))
      (node (ref "U5") (pin "3") (pinfunction "SW_3") (pintype "input"))
    )
    (net (code "56") (name "Net-(U6-CLKOUT)") (class "Default")
      (node (ref "TP4") (pin "TP") (pinfunction "TP_TP") (pintype "input"))
      (node (ref "U6") (pin "1") (pinfunction "CLKOUT_1") (pintype "bidirectional"))
    )
    (net (code "57") (name "Net-(U6-EVI)") (class "Default")
      (node (ref "R13") (pin "1") (pinfunction "1_1") (pintype "passive"))
      (node (ref "U6") (pin "8") (pinfunction "EVI_8") (pintype "bidirectional"))
    )
    (net (code "58") (name "Net-(U6-VBACKUP)") (class "Default")
      (node (ref "C21") (pin "1") (pinfunction "1_1") (pintype "passive"))
      (node (ref "C24") (pin "1") (pinfunction "1_1") (pintype "passive"))
      (node (ref "U6") (pin "6") (pinfunction "VBACKUP_6") (pintype "bidirectional"))
    )
    (net (code "59") (name "Net-(U6-~{INT})") (class "Default")
      (node (ref "TP5") (pin "TP") (pinfunction "TP_TP") (pintype "input"))
      (node (ref "U6") (pin "2") (pinfunction "~{INT}_2") (pintype "bidirectional"))
    )
    (net (code "60") (name "Net-(U7-COMP)") (class "Default")
      (node (ref "C28") (pin "1") (pinfunction "1_1") (pintype "passive"))
      (node (ref "U7") (pin "5") (pinfunction "COMP_5") (pintype "output"))
    )
    (net (code "61") (name "Net-(U7-FB)") (class "Default")
      (node (ref "LED2") (pin "2") (pinfunction "2_2") (pintype "bidirectional"))
      (node (ref "R17") (pin "2") (pinfunction "2_2") (pintype "passive"))
      (node (ref "U7") (pin "6") (pinfunction "FB_6") (pintype "input"))
    )
    (net (code "62") (name "Net-(U7-SW)") (class "Default")
      (node (ref "D4") (pin "+") (pinfunction "+_+") (pintype "passive"))
      (node (ref "L3") (pin "2") (pinfunction "2_2") (pintype "passive"))
      (node (ref "U7") (pin "3") (pinfunction "SW_3") (pintype "input"))
    )
    (net (code "63") (name "SPI0_CE0") (class "Default")
      (node (ref "K1") (pin "24") (pinfunction "24_24") (pintype "passive"))
      (node (ref "P4") (pin "5") (pinfunction "5_5") (pintype "passive"))
    )
    (net (code "64") (name "SPI0_CE1") (class "Default")
      (node (ref "K1") (pin "26") (pinfunction "26_26") (pintype "passive"))
      (node (ref "P7") (pin "5") (pinfunction "5_5") (pintype "passive"))
    )
    (net (code "65") (name "SPI0_MISO") (class "Default")
      (node (ref "K1") (pin "21") (pinfunction "21_21") (pintype "passive"))
      (node (ref "P4") (pin "4") (pinfunction "4_4") (pintype "passive"))
      (node (ref "P7") (pin "4") (pinfunction "4_4") (pintype "passive"))
    )
    (net (code "66") (name "SPI0_MOSI") (class "Default")
      (node (ref "K1") (pin "19") (pinfunction "19_19") (pintype "passive"))
      (node (ref "P4") (pin "7") (pinfunction "7_7") (pintype "passive"))
      (node (ref "P7") (pin "7") (pinfunction "7_7") (pintype "passive"))
    )
    (net (code "67") (name "SPI0_SCLK") (class "Default")
      (node (ref "K1") (pin "23") (pinfunction "23_23") (pintype "passive"))
      (node (ref "P4") (pin "6") (pinfunction "6_6") (pintype "passive"))
      (node (ref "P7") (pin "6") (pinfunction "6_6") (pintype "passive"))
    )
    (net (code "68") (name "UART_RX") (class "Default")
      (node (ref "K1") (pin "10") (pinfunction "10_10") (pintype "passive"))
    )
    (net (code "69") (name "UART_TX") (class "Default")
      (node (ref "K1") (pin "8") (pinfunction "8_8") (pintype "passive"))
    )
    (net (code "70") (name "VOUT") (class "Default")
      (node (ref "L1") (pin "1") (pinfunction "1_1") (pintype "passive"))
      (node (ref "R6") (pin "1") (pinfunction "1_1") (pintype "passive"))
      (node (ref "U3") (pin "8") (pinfunction "SW_8") (pintype "output"))
    )
    (net (code "71") (name "unconnected-(FAN-PadRPM)") (class "Default")
      (node (ref "FAN") (pin "RPM") (pinfunction "RPM_RPM") (pintype "passive"))
    )
    (net (code "72") (name "unconnected-(K1-Pad1)") (class "Default")
      (node (ref "K1") (pin "1") (pinfunction "1_1") (pintype "passive"))
    )
    (net (code "73") (name "unconnected-(P4-Pad1)") (class "Default")
      (node (ref "P4") (pin "1") (pinfunction "1_1") (pintype "passive"))
    )
    (net (code "74") (name "unconnected-(P4-Pad2)") (class "Default")
      (node (ref "P4") (pin "2") (pinfunction "2_2") (pintype "passive"))
    )
    (net (code "75") (name "unconnected-(P7-Pad1)") (class "Default")
      (node (ref "P7") (pin "1") (pinfunction "1_1") (pintype "passive"))
    )
    (net (code "76") (name "unconnected-(P7-Pad2)") (class "Default")
      (node (ref "P7") (pin "2") (pinfunction "2_2") (pintype "passive"))
    )
    (net (code "77") (name "unconnected-(U2-NC-Pad4)") (class "Default")
      (node (ref "U2") (pin "4") (pinfunction "NC_4") (pintype "no_connect"))
    )
  )
)
